# RTU_LMG_LM2596.net
KiCad netlist of a schematic drawn in Altium Designer
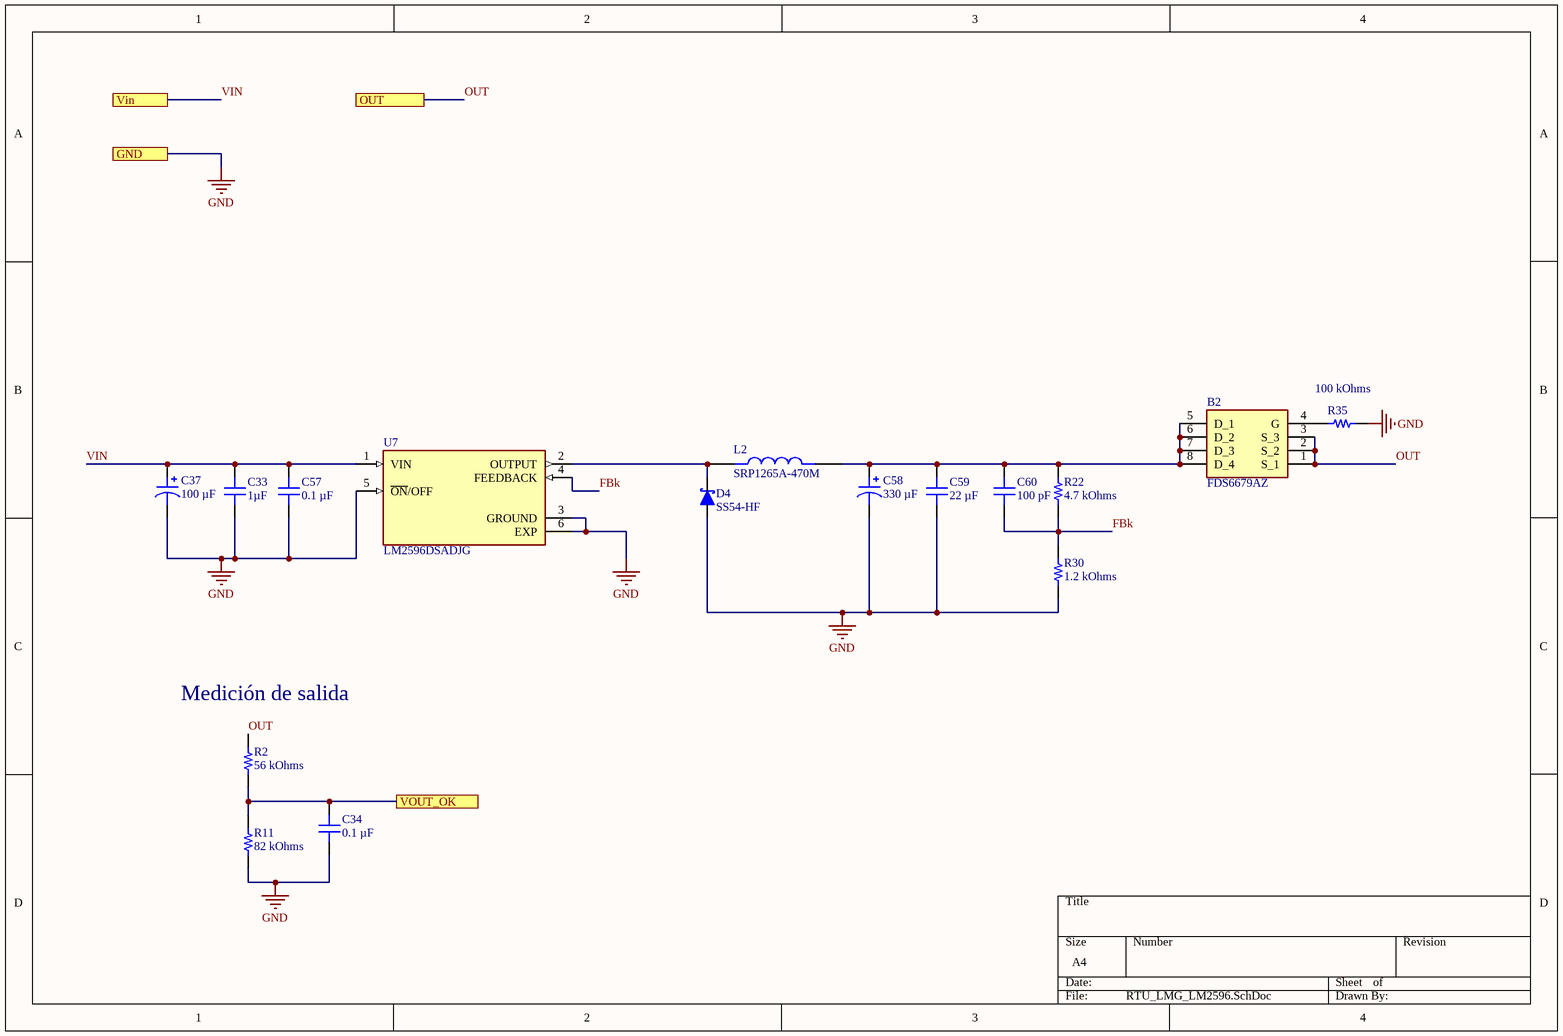
[diagram p0: RTU_LMG_LM2596.SchDoc]

(export (version "E")
  (design (tool "Eeschema 10.0.6"))
  (components
    (comp (ref "B2")
      (value "FDS6679AZ")
      (footprint "SOIC127P600X175-8N")
      (fields (field (name "MOUSER PART NUMBER") "512-FDS6679AZ"))
      (libsource (lib "FDS6679AZ") (part "FDS6679AZ"))
    )
    (comp (ref "C33")
      (value "1µF")
      (footprint "CAP 0603_1608")
      (description "CAP CER 1UF 50V X5R 0603")
      (fields
        (field (name "PART NUMBER") "06035D105MAT2A")
        (field (name "CAPACITANCE") "1µF")
        (field (name "MANUFACTURER") "AVX Corporation")
      )
      (libsource (lib "Celestial Altium Library - altium_library") (part "Capacitor"))
    )
    (comp (ref "C34")
      (value "0.1 µF")
      (footprint "CAP 0402_1005")
      (description "CAP CER 0.1UF 50V X5R 0402")
      (fields
        (field (name "PART NUMBER") "CGA2B3X5R1H104M050BB")
        (field (name "CAPACITANCE") "0.1 µF")
        (field (name "MANUFACTURER") "TDK Corporation")
      )
      (libsource (lib "Celestial Altium Library - altium_library") (part "Capacitor"))
    )
    (comp (ref "C37")
      (value "100 µF")
      (footprint "CAP ALSMD POLY 8.3MM H10.5MM")
      (description "CAP ALUM HYBRD 100UF 20% 35V SMD")
      (fields
        (field (name "PART NUMBER") "HHXD350ARA101MHA0G")
        (field (name "MANUFACTURER") "United Chemi-Con")
      )
      (libsource (lib "Celestial Altium Library - altium_library") (part "Polarised Capacitor"))
    )
    (comp (ref "C57")
      (value "0.1 µF")
      (footprint "CAP 0402_1005")
      (description "CAP CER 0.1UF 50V X5R 0402")
      (fields
        (field (name "PART NUMBER") "CGA2B3X5R1H104M050BB")
        (field (name "CAPACITANCE") "0.1 µF")
        (field (name "MANUFACTURER") "TDK Corporation")
      )
      (libsource (lib "Celestial Altium Library - altium_library") (part "Capacitor"))
    )
    (comp (ref "C58")
      (value "330 µF")
      (footprint "CAP ALSMD 8.3MM H10.5MM")
      (description "CAP ALUM 330UF 20% 16V SMD")
      (fields (field (name "PART NUMBER") "865060353008") (field (name "MANUFACTURER") "Würth Elektronik"))
      (libsource (lib "Celestial Altium Library - altium_library") (part "Polarised Capacitor"))
    )
    (comp (ref "C59")
      (value "22 µF")
      (footprint "CAP 0603_1608")
      (description "CAP CER 22UF 10V X5R 0603")
      (fields
        (field (name "PART NUMBER") "C1608X5R1A226M080AC")
        (field (name "CAPACITANCE") "22 µF")
        (field (name "MANUFACTURER") "TDK Corporation")
      )
      (libsource (lib "Celestial Altium Library - altium_library") (part "Capacitor"))
    )
    (comp (ref "C60")
      (value "100 pF")
      (footprint "CAP 0603_1608")
      (description "CAP CER 100PF 16V X7R 0603")
      (fields
        (field (name "PART NUMBER") "885012206028")
        (field (name "CAPACITANCE") "100 pF")
        (field (name "MANUFACTURER") "Würth Elektronik")
      )
      (libsource (lib "Celestial Altium Library - altium_library") (part "Capacitor"))
    )
    (comp (ref "D4")
      (value "SS54-HF")
      (footprint "DIOM5025X220N")
      (description "Diode Schottky 40 V 5A Surface Mount DO-214AC (SMA)")
      (fields (field (name "MF") "Comchip Technology"))
      (libsource (lib "SS54-HF") (part "SS54-HF"))
    )
    (comp (ref "L2")
      (value "SRP1265A-470M")
      (footprint "IND_SRP1265A-470M")
      (description "Inductor,Shielded Power,AEC-Q200,47uH 20% SMT 1265 ¦ Bourns SRP1265A-470M")
      (fields (field (name "MF") "Bourns"))
      (libsource (lib "SRP1265A-470M") (part "SRP1265A-470M"))
    )
    (comp (ref "R2")
      (value "56 kOhms")
      (footprint "YAGEO RES 0402_1005")
      (description "RES 56K OHM 1% 1/16W 0402")
      (fields (field (name "PART NUMBER") "RC0402FR-0756KL") (field (name "MANUFACTURER") "Yageo"))
      (libsource (lib "Celestial Altium Library - altium_library") (part "Resistor"))
    )
    (comp (ref "R11")
      (value "82 kOhms")
      (footprint "YAGEO RES 0402_1005")
      (description "RES 82K OHM 1% 1/16W 0402")
      (fields (field (name "PART NUMBER") "RC0402FR-0782KL") (field (name "MANUFACTURER") "Yageo"))
      (libsource (lib "Celestial Altium Library - altium_library") (part "Resistor"))
    )
    (comp (ref "R22")
      (value "4.7 kOhms")
      (footprint "YAGEO RES 0603_1608")
      (description "RES SMD 4.7K OHM 1% 1/10W 0603")
      (fields (field (name "PART NUMBER") "RT0603FRE074K7L") (field (name "MANUFACTURER") "Yageo"))
      (libsource (lib "Celestial Altium Library - altium_library") (part "Resistor"))
    )
    (comp (ref "R30")
      (value "1.2 kOhms")
      (footprint "YAGEO RES 0603_1608")
      (description "RES SMD 1.2K OHM 1% 1/10W 0603")
      (fields (field (name "PART NUMBER") "RT0603FRE071K2L") (field (name "MANUFACTURER") "Yageo"))
      (libsource (lib "Celestial Altium Library - altium_library") (part "Resistor"))
    )
    (comp (ref "R35")
      (value "100 kOhms")
      (footprint "RES 0603_1608")
      (description "RES 100K OHM 0.1% 1/16W 0603")
      (fields
        (field (name "PART NUMBER") "RNCS0603BKE100K")
        (field (name "MANUFACTURER") "Stackpole Electronics Inc")
      )
      (libsource (lib "Celestial Altium Library - altium_library") (part "Resistor"))
    )
    (comp (ref "U7")
      (value "LM2596DSADJG")
      (footprint "CONV_LM2596DSADJG")
      (fields (field (name "MF") "ON Semiconductor"))
      (libsource (lib "LM2596DSADJG") (part "LM2596DSADJG"))
    )
  )
  (nets
    (net (code "1") (name "/FBk") (class "Default")
      (node (ref "C60") (pin "1") (pinfunction "1_1") (pintype "passive"))
      (node (ref "R22") (pin "1") (pinfunction "1_1") (pintype "passive"))
      (node (ref "R30") (pin "2") (pinfunction "2_2") (pintype "passive"))
      (node (ref "U7") (pin "4") (pinfunction "FEEDBACK_4") (pintype "input"))
    )
    (net (code "2") (name "/OUT") (class "Default")
      (node (ref "B2") (pin "1") (pinfunction "S_1_1") (pintype "passive"))
      (node (ref "B2") (pin "2") (pinfunction "S_2_2") (pintype "passive"))
      (node (ref "B2") (pin "3") (pinfunction "S_3_3") (pintype "passive"))
      (node (ref "R2") (pin "2") (pinfunction "2_2") (pintype "passive"))
    )
    (net (code "3") (name "/VIN") (class "Default")
      (node (ref "C33") (pin "2") (pinfunction "2_2") (pintype "passive"))
      (node (ref "C37") (pin "1") (pinfunction "1_1") (pintype "passive"))
      (node (ref "C57") (pin "2") (pinfunction "2_2") (pintype "passive"))
      (node (ref "U7") (pin "1") (pinfunction "VIN_1") (pintype "input"))
    )
    (net (code "4") (name "/VOUT_OK") (class "Default")
      (node (ref "C34") (pin "2") (pinfunction "2_2") (pintype "passive"))
      (node (ref "R11") (pin "2") (pinfunction "2_2") (pintype "passive"))
      (node (ref "R2") (pin "1") (pinfunction "1_1") (pintype "passive"))
    )
    (net (code "5") (name "GND") (class "Default")
      (node (ref "C33") (pin "1") (pinfunction "1_1") (pintype "passive"))
      (node (ref "C34") (pin "1") (pinfunction "1_1") (pintype "passive"))
      (node (ref "C37") (pin "2") (pinfunction "2_2") (pintype "passive"))
      (node (ref "C57") (pin "1") (pinfunction "1_1") (pintype "passive"))
      (node (ref "C58") (pin "2") (pinfunction "2_2") (pintype "passive"))
      (node (ref "C59") (pin "1") (pinfunction "1_1") (pintype "passive"))
      (node (ref "D4") (pin "2") (pinfunction "A_2") (pintype "bidirectional"))
      (node (ref "R11") (pin "1") (pinfunction "1_1") (pintype "passive"))
      (node (ref "R30") (pin "1") (pinfunction "1_1") (pintype "passive"))
      (node (ref "R35") (pin "2") (pinfunction "2_2") (pintype "passive"))
      (node (ref "U7") (pin "3") (pinfunction "GROUND_3") (pintype "power_in"))
      (node (ref "U7") (pin "5") (pinfunction "~{ON}/OFF_5") (pintype "input"))
      (node (ref "U7") (pin "6") (pinfunction "EXP_6") (pintype "power_in"))
    )
    (net (code "6") (name "Net-(B2-D_1)") (class "Default")
      (node (ref "B2") (pin "5") (pinfunction "D_1_5") (pintype "passive"))
      (node (ref "B2") (pin "6") (pinfunction "D_2_6") (pintype "passive"))
      (node (ref "B2") (pin "7") (pinfunction "D_3_7") (pintype "passive"))
      (node (ref "B2") (pin "8") (pinfunction "D_4_8") (pintype "passive"))
      (node (ref "C58") (pin "1") (pinfunction "1_1") (pintype "passive"))
      (node (ref "C59") (pin "2") (pinfunction "2_2") (pintype "passive"))
      (node (ref "C60") (pin "2") (pinfunction "2_2") (pintype "passive"))
      (node (ref "L2") (pin "2") (pinfunction "2_2") (pintype "passive"))
      (node (ref "R22") (pin "2") (pinfunction "2_2") (pintype "passive"))
    )
    (net (code "7") (name "Net-(B2-G)") (class "Default")
      (node (ref "B2") (pin "4") (pinfunction "G_4") (pintype "passive"))
      (node (ref "R35") (pin "1") (pinfunction "1_1") (pintype "passive"))
    )
    (net (code "8") (name "Net-(D4-K)") (class "Default")
      (node (ref "D4") (pin "1") (pinfunction "K_1") (pintype "bidirectional"))
      (node (ref "L2") (pin "1") (pinfunction "1_1") (pintype "passive"))
      (node (ref "U7") (pin "2") (pinfunction "OUTPUT_2") (pintype "output"))
    )
  )
)
